# Screen_Driver.net
KiCad netlist of a schematic drawn in Altium Designer
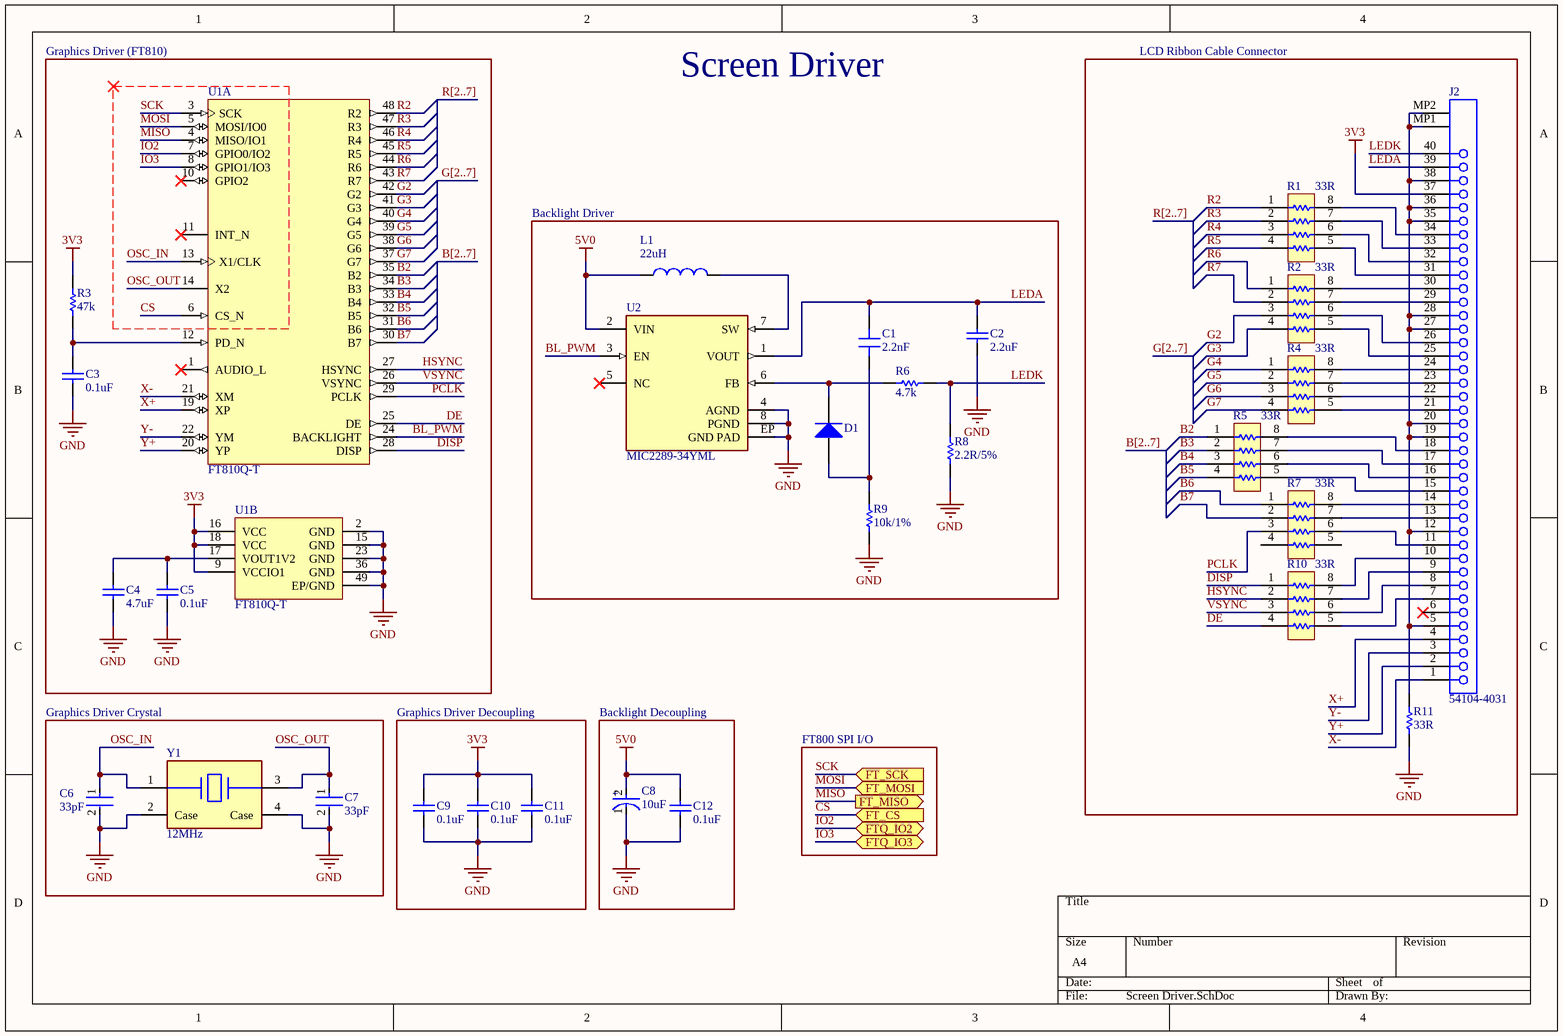
[diagram p0: Screen Driver.SchDoc]

(export (version "E")
  (design (tool "Eeschema 10.0.6"))
  (components
    (comp (ref "C1")
      (value "2.2nF")
      (footprint "0805")
      (description "CAP CER 2200PF 50V X7R 0805")
      (fields
        (field (name "MANUFACTURER") "Samsung")
        (field (name "MANUFACTURER PART NUMBER") "CL21B222KBANNNC")
      )
      (libsource (lib "Dummy Parts") (part "Capacitor - Ceramic"))
    )
    (comp (ref "C2")
      (value "2.2uF")
      (footprint "CAPC3225X270X30ML30")
      (description "Chip Capacitor, 22 uF, +/- 10%, 25 V, -55 to 125 degC, 1210 (3225 Metric), RoHS, Tape and Reel")
      (fields
        (field (name "MANUFACTURER") "Murata")
        (field (name "MANUFACTURER PART NUMBER") "GRM32ER71E226KE15L")
      )
      (libsource (lib "Altium Content Vault") (part "CAP-NP-2"))
    )
    (comp (ref "C3")
      (value "0.1uF")
      (footprint "CAPC2013X88X50NL20T25")
      (fields
        (field (name "PART NUMBER") "C0805C104K5RACTU")
        (field (name "MANUFACTURER") "Kemet")
        (field (name "TOLERANCE") "10%")
      )
      (libsource (lib "Altium Content Vault") (part "CAP"))
    )
    (comp (ref "C4")
      (value "4.7uF")
      (footprint "CAPC2113X120X50LL20T30")
      (fields
        (field (name "PART NUMBER") "TAJR475K006RNJ")
        (field (name "MANUFACTURER") "AVX Interconnect / Elco")
        (field (name "TOLERANCE") "10%")
      )
      (libsource (lib "Altium Content Vault") (part "CAP"))
    )
    (comp (ref "C5")
      (value "0.1uF")
      (footprint "CAPC2013X88X50NL20T25")
      (fields
        (field (name "PART NUMBER") "C0805C104K5RACTU")
        (field (name "MANUFACTURER") "Kemet")
        (field (name "TOLERANCE") "10%")
      )
      (libsource (lib "Altium Content Vault") (part "CAP"))
    )
    (comp (ref "C6")
      (value "33pF")
      (footprint "FP-CL21-IPC_B")
      (description "CL21 Series 0805 33pF 50V ±5% Tolerance C0G Multilayer Ceramic Chip Capacitor")
      (fields (field (name "TOLERANCE") "5%") (field (name "VOLTAGE") "50V"))
      (libsource (lib "Altium Content Vault") (part "b4654b650e69147ec39a6b967a45e02"))
    )
    (comp (ref "C7")
      (value "33pF")
      (footprint "FP-CL21-IPC_B")
      (description "CL21 Series 0805 33pF 50V ±5% Tolerance C0G Multilayer Ceramic Chip Capacitor")
      (fields (field (name "TOLERANCE") "5%") (field (name "VOLTAGE") "50V"))
      (libsource (lib "Altium Content Vault") (part "b4654b650e69147ec39a6b967a45e02"))
    )
    (comp (ref "C8")
      (value "10uF")
      (footprint "FP-T491C-MFG")
      (description "CAP TANT 10UF 10% 25V 2312")
      (fields (field (name "TOLERANCE") "10%") (field (name "MANUFACTURER PART NUMBER") "T491C106K025AT"))
      (libsource (lib "Altium Content Vault") (part "203bc49f2ac43e59fd269a8c329ed05"))
    )
    (comp (ref "C9")
      (value "0.1uF")
      (footprint "CAPC2013X88X50NL20T25")
      (fields
        (field (name "PART NUMBER") "C0805C104K5RACTU")
        (field (name "MANUFACTURER") "Kemet")
        (field (name "TOLERANCE") "10%")
      )
      (libsource (lib "Altium Content Vault") (part "CAP"))
    )
    (comp (ref "C10")
      (value "0.1uF")
      (footprint "CAPC2013X88X50NL20T25")
      (fields
        (field (name "PART NUMBER") "C0805C104K5RACTU")
        (field (name "MANUFACTURER") "Kemet")
        (field (name "TOLERANCE") "10%")
      )
      (libsource (lib "Altium Content Vault") (part "CAP"))
    )
    (comp (ref "C11")
      (value "0.1uF")
      (footprint "CAPC2013X88X50NL20T25")
      (fields
        (field (name "PART NUMBER") "C0805C104K5RACTU")
        (field (name "MANUFACTURER") "Kemet")
        (field (name "TOLERANCE") "10%")
      )
      (libsource (lib "Altium Content Vault") (part "CAP"))
    )
    (comp (ref "C12")
      (value "0.1uF")
      (footprint "CAPC2013X88X50NL20T25")
      (fields
        (field (name "PART NUMBER") "C0805C104K5RACTU")
        (field (name "MANUFACTURER") "Kemet")
        (field (name "TOLERANCE") "10%")
      )
      (libsource (lib "Altium Content Vault") (part "CAP"))
    )
    (comp (ref "D1")
      (value "1N4148WS-7-F")
      (footprint "DIOD-SOD323-2-A_V")
      (description "Fast Switching Diode, 75 V, 0.3 A, -65 to 150 degC, 2-Pin SOD323, RoHS, Tape and Reel")
      (fields (field (name "MANUFACTURER") "Diodes") (field (name "VOLTAGE") "75V"))
      (libsource (lib "Altium Content Vault") (part "D-AK-2"))
    )
    (comp (ref "J2")
      (value "54104-4031")
      (footprint "MOLX-54104-4031")
      (fields (field (name "MANUFACTURER") "Molex"))
      (libsource (lib "Altium Content Vault") (part "MOLX-54104-4031"))
    )
    (comp (ref "L1")
      (value "22uH")
      (footprint "*INDC2012X145N")
      (description "POWER INDUCTOR, 22UH, 0.135A, 10%, 16MHz")
      (fields
        (field (name "MANUFACTURER") "Taiyo Yuden")
        (field (name "MANUFACTURER PART NUMBER") "CB2012T220K")
      )
      (libsource (lib "CB2012T220K") (part "CB2012T220K"))
    )
    (comp (ref "R1")
      (value "33R")
      (footprint "PNSC-EXB-38V103JV-8_M")
      (description "Chip Resistor, 10 KOhm, +/- 5%, -55 to 125degC, 8-Pin SMD (4 X 0603), RoHS, Tape and Reel")
      (fields
        (field (name "MANUFACTURER") "Panasonic")
        (field (name "MANUFACTURER PART NUMBER") "EXB-38V103JV")
      )
      (libsource (lib "Altium Content Vault") (part "RES-P-8"))
    )
    (comp (ref "R2")
      (value "33R")
      (footprint "PNSC-EXB-38V103JV-8_M")
      (description "Chip Resistor, 10 KOhm, +/- 5%, -55 to 125degC, 8-Pin SMD (4 X 0603), RoHS, Tape and Reel")
      (fields
        (field (name "MANUFACTURER") "Panasonic")
        (field (name "MANUFACTURER PART NUMBER") "EXB-38V103JV")
      )
      (libsource (lib "Altium Content Vault") (part "RES-P-8"))
    )
    (comp (ref "R3")
      (value "47k")
      (footprint "0805")
      (description "Thin Film Resistors - SMD 0805 1/8W 3.3Kohms")
      (fields
        (field (name "MANUFACTURER") "Panasonic")
        (field (name "MANUFACTURER PART NUMBER") "ERA-6AEB332V")
      )
      (libsource (lib "Dummy Parts") (part "Resistor"))
    )
    (comp (ref "R4")
      (value "33R")
      (footprint "PNSC-EXB-38V103JV-8_M")
      (description "Chip Resistor, 10 KOhm, +/- 5%, -55 to 125degC, 8-Pin SMD (4 X 0603), RoHS, Tape and Reel")
      (fields
        (field (name "MANUFACTURER") "Panasonic")
        (field (name "MANUFACTURER PART NUMBER") "EXB-38V103JV")
      )
      (libsource (lib "Altium Content Vault") (part "RES-P-8"))
    )
    (comp (ref "R5")
      (value "33R")
      (footprint "PNSC-EXB-38V103JV-8_M")
      (description "Chip Resistor, 10 KOhm, +/- 5%, -55 to 125degC, 8-Pin SMD (4 X 0603), RoHS, Tape and Reel")
      (fields
        (field (name "MANUFACTURER") "Panasonic")
        (field (name "MANUFACTURER PART NUMBER") "EXB-38V103JV")
      )
      (libsource (lib "Altium Content Vault") (part "RES-P-8"))
    )
    (comp (ref "R6")
      (value "4.7k")
      (footprint "0805")
      (description "Thick Film Resistors - SMD 0805 4.7Kohms 5% AEC-Q200")
      (fields
        (field (name "MANUFACTURER") "Panasonic")
        (field (name "MANUFACTURER PART NUMBER") "ERJ-6GEYJ472V")
      )
      (libsource (lib "Dummy Parts") (part "Resistor"))
    )
    (comp (ref "R7")
      (value "33R")
      (footprint "PNSC-EXB-38V103JV-8_M")
      (description "Chip Resistor, 10 KOhm, +/- 5%, -55 to 125degC, 8-Pin SMD (4 X 0603), RoHS, Tape and Reel")
      (fields
        (field (name "MANUFACTURER") "Panasonic")
        (field (name "MANUFACTURER PART NUMBER") "EXB-38V103JV")
      )
      (libsource (lib "Altium Content Vault") (part "RES-P-8"))
    )
    (comp (ref "R8")
      (value "2.2R/5%")
      (footprint "0805")
      (description "Resistor;  Thick Film;  Res 2.2 Ohms;  Pwr-Rtg 0.125 W;  Tol 5%;  SMT;  0805;  Tape & Reel")
      (fields
        (field (name "MANUFACTURER") "Panasonic")
        (field (name "MANUFACTURER PART NUMBER") "ERJ-6GEYJ2R2V")
      )
      (libsource (lib "Dummy Parts") (part "Resistor"))
    )
    (comp (ref "R9")
      (value "10k/1%")
      (footprint "0805")
      (fields
        (field (name "MANUFACTURER") "Panasonic")
        (field (name "MANUFACTURER PART NUMBER") "ERJ-6ENF1002V")
        (field (name "TOLERANCE") "1%")
      )
      (libsource (lib "Dummy Parts") (part "Resistor"))
    )
    (comp (ref "R10")
      (value "33R")
      (footprint "PNSC-EXB-38V103JV-8_M")
      (description "Chip Resistor, 10 KOhm, +/- 5%, -55 to 125degC, 8-Pin SMD (4 X 0603), RoHS, Tape and Reel")
      (fields
        (field (name "MANUFACTURER") "Panasonic")
        (field (name "MANUFACTURER PART NUMBER") "EXB-38V103JV")
      )
      (libsource (lib "Altium Content Vault") (part "RES-P-8"))
    )
    (comp (ref "R11")
      (value "33R")
      (footprint "0805")
      (description "Res Thick Film 0805 33 Ohm 1% 0.125W(1/8W) ±100ppm/C Molded SMD Automotive Punched T/R")
      (fields
        (field (name "MANUFACTURER") "Panasonic")
        (field (name "MANUFACTURER PART NUMBER") "ERJ-6ENF33R0V")
      )
      (libsource (lib "Dummy Parts") (part "Resistor"))
    )
    (comp (ref "U1")
      (value "FT810Q-T")
      (footprint "VQFN-48_5.2x5.2EP")
      (fields (field (name "MANUFACTURER") "FTDI"))
      (libsource (lib "Altium Content Vault") (part "FT810Q"))
    )
    (comp (ref "U2")
      (value "MIC2289")
      (footprint "MIC2289")
      (fields
        (field (name "MANUFACTURER") "Microchip")
        (field (name "MOUSER PART NUMBER") "998-MIC2289-34YMLTR")
        (field (name "DIGIKEY PART NUMBER") "576-1732-1-ND")
        (field (name "PART NUMBER") "MIC2289-34YML")
      )
      (libsource (lib "MIC2289") (part "MIC2289"))
    )
    (comp (ref "Y1")
      (value "12MHz")
      (footprint "FP-FL1200112-MFG")
      (description "CRYSTAL 12MHZ 18PF SMD")
      (fields (field (name "MANUFACTURER") "Diodes") (field (name "MANUFACTURER PART NUMBER") "FL1200112"))
      (libsource (lib "Altium Content Vault") (part "5207c8a21b287eb3b87797a81180633"))
    )
  )
  (nets
    (net (code "1") (name "/B2") (class "Default")
      (node (ref "R5") (pin "1") (pinfunction "1_1") (pintype "passive"))
      (node (ref "U1") (pin "35") (pinfunction "B2_35") (pintype "output"))
    )
    (net (code "2") (name "/B3") (class "Default")
      (node (ref "R5") (pin "2") (pinfunction "2_2") (pintype "passive"))
      (node (ref "U1") (pin "34") (pinfunction "B3_34") (pintype "output"))
    )
    (net (code "3") (name "/B4") (class "Default")
      (node (ref "R5") (pin "3") (pinfunction "3_3") (pintype "passive"))
      (node (ref "U1") (pin "33") (pinfunction "B4_33") (pintype "output"))
    )
    (net (code "4") (name "/B5") (class "Default")
      (node (ref "R5") (pin "4") (pinfunction "4_4") (pintype "passive"))
      (node (ref "U1") (pin "32") (pinfunction "B5_32") (pintype "output"))
    )
    (net (code "5") (name "/B6") (class "Default")
      (node (ref "R7") (pin "1") (pinfunction "1_1") (pintype "passive"))
      (node (ref "U1") (pin "31") (pinfunction "B6_31") (pintype "output"))
    )
    (net (code "6") (name "/B7") (class "Default")
      (node (ref "R7") (pin "2") (pinfunction "2_2") (pintype "passive"))
      (node (ref "U1") (pin "30") (pinfunction "B7_30") (pintype "output"))
    )
    (net (code "7") (name "/BL_PWM") (class "Default")
      (node (ref "U1") (pin "24") (pinfunction "BACKLIGHT_24") (pintype "output"))
      (node (ref "U2") (pin "3") (pinfunction "EN_3") (pintype "input"))
    )
    (net (code "9") (name "/CS") (class "Default")
      (node (ref "U1") (pin "6") (pinfunction "CS_N_6") (pintype "input"))
    )
    (net (code "10") (name "/DE") (class "Default")
      (node (ref "R10") (pin "4") (pinfunction "4_4") (pintype "passive"))
      (node (ref "U1") (pin "25") (pinfunction "DE_25") (pintype "output"))
    )
    (net (code "11") (name "/DISP") (class "Default")
      (node (ref "R10") (pin "1") (pinfunction "1_1") (pintype "passive"))
      (node (ref "U1") (pin "28") (pinfunction "DISP_28") (pintype "output"))
    )
    (net (code "12") (name "/G2") (class "Default")
      (node (ref "R2") (pin "3") (pinfunction "3_3") (pintype "passive"))
      (node (ref "U1") (pin "42") (pinfunction "G2_42") (pintype "output"))
    )
    (net (code "13") (name "/G3") (class "Default")
      (node (ref "R2") (pin "4") (pinfunction "4_4") (pintype "passive"))
      (node (ref "U1") (pin "41") (pinfunction "G3_41") (pintype "output"))
    )
    (net (code "14") (name "/G4") (class "Default")
      (node (ref "R4") (pin "1") (pinfunction "1_1") (pintype "passive"))
      (node (ref "U1") (pin "40") (pinfunction "G4_40") (pintype "output"))
    )
    (net (code "15") (name "/G5") (class "Default")
      (node (ref "R4") (pin "2") (pinfunction "2_2") (pintype "passive"))
      (node (ref "U1") (pin "39") (pinfunction "G5_39") (pintype "output"))
    )
    (net (code "16") (name "/G6") (class "Default")
      (node (ref "R4") (pin "3") (pinfunction "3_3") (pintype "passive"))
      (node (ref "U1") (pin "38") (pinfunction "G6_38") (pintype "output"))
    )
    (net (code "17") (name "/G7") (class "Default")
      (node (ref "R4") (pin "4") (pinfunction "4_4") (pintype "passive"))
      (node (ref "U1") (pin "37") (pinfunction "G7_37") (pintype "output"))
    )
    (net (code "19") (name "/HSYNC") (class "Default")
      (node (ref "R10") (pin "2") (pinfunction "2_2") (pintype "passive"))
      (node (ref "U1") (pin "27") (pinfunction "HSYNC_27") (pintype "output"))
    )
    (net (code "20") (name "/IO2") (class "Default")
      (node (ref "U1") (pin "7") (pinfunction "GPIO0/IO2_7") (pintype "bidirectional"))
    )
    (net (code "21") (name "/IO3") (class "Default")
      (node (ref "U1") (pin "8") (pinfunction "GPIO1/IO3_8") (pintype "bidirectional"))
    )
    (net (code "22") (name "/LEDA") (class "Default")
      (node (ref "C1") (pin "2") (pinfunction "2_2") (pintype "passive"))
      (node (ref "C2") (pin "2") (pinfunction "2_2") (pintype "passive"))
      (node (ref "J2") (pin "39") (pinfunction "39_39") (pintype "passive"))
      (node (ref "U2") (pin "1") (pinfunction "VOUT_1") (pintype "output"))
    )
    (net (code "23") (name "/LEDK") (class "Default")
      (node (ref "J2") (pin "40") (pinfunction "40_40") (pintype "passive"))
      (node (ref "R6") (pin "1") (pinfunction "1_1") (pintype "passive"))
      (node (ref "R8") (pin "1") (pinfunction "1_1") (pintype "passive"))
    )
    (net (code "24") (name "/MISO") (class "Default")
      (node (ref "U1") (pin "4") (pinfunction "MISO/IO1_4") (pintype "bidirectional"))
    )
    (net (code "25") (name "/MOSI") (class "Default")
      (node (ref "U1") (pin "5") (pinfunction "MOSI/IO0_5") (pintype "bidirectional"))
    )
    (net (code "26") (name "/OSC_IN") (class "Default")
      (node (ref "C6") (pin "1") (pinfunction "1_1") (pintype "passive"))
      (node (ref "U1") (pin "13") (pinfunction "X1/CLK_13") (pintype "input"))
      (node (ref "Y1") (pin "1") (pinfunction "1_Xtal_1") (pintype "passive"))
    )
    (net (code "27") (name "/OSC_OUT") (class "Default")
      (node (ref "C7") (pin "1") (pinfunction "1_1") (pintype "passive"))
      (node (ref "U1") (pin "14") (pinfunction "X2_14") (pintype "passive"))
      (node (ref "Y1") (pin "3") (pinfunction "2_Xtal_3") (pintype "passive"))
    )
    (net (code "28") (name "/PCLK") (class "Default")
      (node (ref "R7") (pin "3") (pinfunction "3_3") (pintype "passive"))
      (node (ref "U1") (pin "29") (pinfunction "PCLK_29") (pintype "output"))
    )
    (net (code "29") (name "/R2") (class "Default")
      (node (ref "R1") (pin "1") (pinfunction "1_1") (pintype "passive"))
      (node (ref "U1") (pin "48") (pinfunction "R2_48") (pintype "output"))
    )
    (net (code "30") (name "/R3") (class "Default")
      (node (ref "R1") (pin "2") (pinfunction "2_2") (pintype "passive"))
      (node (ref "U1") (pin "47") (pinfunction "R3_47") (pintype "output"))
    )
    (net (code "31") (name "/R4") (class "Default")
      (node (ref "R1") (pin "3") (pinfunction "3_3") (pintype "passive"))
      (node (ref "U1") (pin "46") (pinfunction "R4_46") (pintype "output"))
    )
    (net (code "32") (name "/R5") (class "Default")
      (node (ref "R1") (pin "4") (pinfunction "4_4") (pintype "passive"))
      (node (ref "U1") (pin "45") (pinfunction "R5_45") (pintype "output"))
    )
    (net (code "33") (name "/R6") (class "Default")
      (node (ref "R2") (pin "1") (pinfunction "1_1") (pintype "passive"))
      (node (ref "U1") (pin "44") (pinfunction "R6_44") (pintype "output"))
    )
    (net (code "34") (name "/R7") (class "Default")
      (node (ref "R2") (pin "2") (pinfunction "2_2") (pintype "passive"))
      (node (ref "U1") (pin "43") (pinfunction "R7_43") (pintype "output"))
    )
    (net (code "36") (name "/SCK") (class "Default")
      (node (ref "U1") (pin "3") (pinfunction "SCK_3") (pintype "input"))
    )
    (net (code "37") (name "/VSYNC") (class "Default")
      (node (ref "R10") (pin "3") (pinfunction "3_3") (pintype "passive"))
      (node (ref "U1") (pin "26") (pinfunction "VSYNC_26") (pintype "output"))
    )
    (net (code "38") (name "/X+") (class "Default")
      (node (ref "J2") (pin "4") (pinfunction "4_4") (pintype "passive"))
      (node (ref "U1") (pin "19") (pinfunction "XP_19") (pintype "bidirectional"))
    )
    (net (code "39") (name "/X-") (class "Default")
      (node (ref "J2") (pin "1") (pinfunction "1_1") (pintype "passive"))
      (node (ref "U1") (pin "21") (pinfunction "XM_21") (pintype "bidirectional"))
    )
    (net (code "40") (name "/Y+") (class "Default")
      (node (ref "J2") (pin "2") (pinfunction "2_2") (pintype "passive"))
      (node (ref "U1") (pin "20") (pinfunction "YP_20") (pintype "bidirectional"))
    )
    (net (code "41") (name "/Y-") (class "Default")
      (node (ref "J2") (pin "3") (pinfunction "3_3") (pintype "passive"))
      (node (ref "U1") (pin "22") (pinfunction "YM_22") (pintype "bidirectional"))
    )
    (net (code "42") (name "3V3") (class "Default")
      (node (ref "C10") (pin "2") (pinfunction "2_2") (pintype "passive"))
      (node (ref "C11") (pin "2") (pinfunction "2_2") (pintype "passive"))
      (node (ref "C9") (pin "2") (pinfunction "2_2") (pintype "passive"))
      (node (ref "J2") (pin "37") (pinfunction "37_37") (pintype "passive"))
      (node (ref "R3") (pin "2") (pinfunction "2_2") (pintype "passive"))
      (node (ref "U1") (pin "16") (pinfunction "VCC_16") (pintype "power_in"))
      (node (ref "U1") (pin "18") (pinfunction "VCC_18") (pintype "power_in"))
      (node (ref "U1") (pin "9") (pinfunction "VCCIO1_9") (pintype "power_in"))
    )
    (net (code "43") (name "5V0") (class "Default")
      (node (ref "C12") (pin "2") (pinfunction "2_2") (pintype "passive"))
      (node (ref "C8") (pin "2") (pinfunction "A_2") (pintype "passive"))
      (node (ref "L1") (pin "1") (pinfunction "1_1") (pintype "passive"))
      (node (ref "U2") (pin "2") (pinfunction "VIN_2") (pintype "power_in"))
    )
    (net (code "44") (name "GND") (class "Default")
      (node (ref "C10") (pin "1") (pinfunction "1_1") (pintype "passive"))
      (node (ref "C11") (pin "1") (pinfunction "1_1") (pintype "passive"))
      (node (ref "C12") (pin "1") (pinfunction "1_1") (pintype "passive"))
      (node (ref "C2") (pin "1") (pinfunction "1_1") (pintype "passive"))
      (node (ref "C3") (pin "1") (pinfunction "1_1") (pintype "passive"))
      (node (ref "C4") (pin "1") (pinfunction "1_1") (pintype "passive"))
      (node (ref "C5") (pin "1") (pinfunction "1_1") (pintype "passive"))
      (node (ref "C6") (pin "2") (pinfunction "2_2") (pintype "passive"))
      (node (ref "C7") (pin "2") (pinfunction "2_2") (pintype "passive"))
      (node (ref "C8") (pin "1") (pinfunction "C_1") (pintype "passive"))
      (node (ref "C9") (pin "1") (pinfunction "1_1") (pintype "passive"))
      (node (ref "R11") (pin "1") (pinfunction "1_1") (pintype "passive"))
      (node (ref "R8") (pin "2") (pinfunction "2_2") (pintype "passive"))
      (node (ref "R9") (pin "1") (pinfunction "1_1") (pintype "passive"))
      (node (ref "U1") (pin "15") (pinfunction "GND_15") (pintype "power_in"))
      (node (ref "U1") (pin "2") (pinfunction "GND_2") (pintype "power_in"))
      (node (ref "U1") (pin "23") (pinfunction "GND_23") (pintype "power_in"))
      (node (ref "U1") (pin "36") (pinfunction "GND_36") (pintype "power_in"))
      (node (ref "U1") (pin "49") (pinfunction "EP/GND_49") (pintype "power_in"))
      (node (ref "U2") (pin "4") (pinfunction "AGND_4") (pintype "power_in"))
      (node (ref "U2") (pin "8") (pinfunction "PGND_8") (pintype "power_in"))
      (node (ref "U2") (pin "EP") (pinfunction "GND_PAD_EP") (pintype "power_in"))
      (node (ref "Y1") (pin "2") (pinfunction "Case_2") (pintype "passive"))
      (node (ref "Y1") (pin "4") (pinfunction "Case_4") (pintype "passive"))
    )
    (net (code "45") (name "Net-(D1-A)") (class "Default")
      (node (ref "C1") (pin "1") (pinfunction "1_1") (pintype "passive"))
      (node (ref "D1") (pin "1") (pinfunction "A_1") (pintype "passive"))
      (node (ref "R9") (pin "2") (pinfunction "2_2") (pintype "passive"))
    )
    (net (code "46") (name "Net-(D1-K)") (class "Default")
      (node (ref "D1") (pin "2") (pinfunction "K_2") (pintype "passive"))
      (node (ref "R6") (pin "2") (pinfunction "2_2") (pintype "passive"))
      (node (ref "U2") (pin "6") (pinfunction "FB_6") (pintype "input"))
    )
    (net (code "47") (name "Net-(J2-Pad7)") (class "Default")
      (node (ref "J2") (pin "7") (pinfunction "7_7") (pintype "passive"))
      (node (ref "R10") (pin "5") (pinfunction "5_5") (pintype "passive"))
    )
    (net (code "48") (name "Net-(J2-Pad8)") (class "Default")
      (node (ref "J2") (pin "8") (pinfunction "8_8") (pintype "passive"))
      (node (ref "R10") (pin "6") (pinfunction "6_6") (pintype "passive"))
    )
    (net (code "49") (name "Net-(J2-Pad9)") (class "Default")
      (node (ref "J2") (pin "9") (pinfunction "9_9") (pintype "passive"))
      (node (ref "R10") (pin "7") (pinfunction "7_7") (pintype "passive"))
    )
    (net (code "50") (name "Net-(J2-Pad10)") (class "Default")
      (node (ref "J2") (pin "10") (pinfunction "10_10") (pintype "passive"))
      (node (ref "R10") (pin "8") (pinfunction "8_8") (pintype "passive"))
    )
    (net (code "51") (name "Net-(J2-Pad11)") (class "Default")
      (node (ref "J2") (pin "11") (pinfunction "11_11") (pintype "passive"))
      (node (ref "R7") (pin "6") (pinfunction "6_6") (pintype "passive"))
    )
    (net (code "52") (name "Net-(J2-Pad12)") (class "Default")
      (node (ref "J2") (pin "12") (pinfunction "12_12") (pintype "passive"))
      (node (ref "J2") (pin "19") (pinfunction "19_19") (pintype "passive"))
      (node (ref "J2") (pin "20") (pinfunction "20_20") (pintype "passive"))
      (node (ref "J2") (pin "27") (pinfunction "27_27") (pintype "passive"))
      (node (ref "J2") (pin "28") (pinfunction "28_28") (pintype "passive"))
      (node (ref "J2") (pin "35") (pinfunction "35_35") (pintype "passive"))
      (node (ref "J2") (pin "36") (pinfunction "36_36") (pintype "passive"))
      (node (ref "J2") (pin "38") (pinfunction "38_38") (pintype "passive"))
      (node (ref "J2") (pin "5") (pinfunction "5_5") (pintype "passive"))
      (node (ref "J2") (pin "MP1") (pinfunction "MP1_MP1") (pintype "passive"))
      (node (ref "J2") (pin "MP2") (pinfunction "MP2_MP2") (pintype "passive"))
      (node (ref "R11") (pin "2") (pinfunction "2_2") (pintype "passive"))
    )
    (net (code "53") (name "Net-(J2-Pad13)") (class "Default")
      (node (ref "J2") (pin "13") (pinfunction "13_13") (pintype "passive"))
      (node (ref "R7") (pin "7") (pinfunction "7_7") (pintype "passive"))
    )
    (net (code "54") (name "Net-(J2-Pad14)") (class "Default")
      (node (ref "J2") (pin "14") (pinfunction "14_14") (pintype "passive"))
      (node (ref "R7") (pin "8") (pinfunction "8_8") (pintype "passive"))
    )
    (net (code "55") (name "Net-(J2-Pad15)") (class "Default")
      (node (ref "J2") (pin "15") (pinfunction "15_15") (pintype "passive"))
      (node (ref "R5") (pin "5") (pinfunction "5_5") (pintype "passive"))
    )
    (net (code "56") (name "Net-(J2-Pad16)") (class "Default")
      (node (ref "J2") (pin "16") (pinfunction "16_16") (pintype "passive"))
      (node (ref "R5") (pin "6") (pinfunction "6_6") (pintype "passive"))
    )
    (net (code "57") (name "Net-(J2-Pad17)") (class "Default")
      (node (ref "J2") (pin "17") (pinfunction "17_17") (pintype "passive"))
      (node (ref "R5") (pin "7") (pinfunction "7_7") (pintype "passive"))
    )
    (net (code "58") (name "Net-(J2-Pad18)") (class "Default")
      (node (ref "J2") (pin "18") (pinfunction "18_18") (pintype "passive"))
      (node (ref "R5") (pin "8") (pinfunction "8_8") (pintype "passive"))
    )
    (net (code "59") (name "Net-(J2-Pad21)") (class "Default")
      (node (ref "J2") (pin "21") (pinfunction "21_21") (pintype "passive"))
      (node (ref "R4") (pin "5") (pinfunction "5_5") (pintype "passive"))
    )
    (net (code "60") (name "Net-(J2-Pad22)") (class "Default")
      (node (ref "J2") (pin "22") (pinfunction "22_22") (pintype "passive"))
      (node (ref "R4") (pin "6") (pinfunction "6_6") (pintype "passive"))
    )
    (net (code "61") (name "Net-(J2-Pad23)") (class "Default")
      (node (ref "J2") (pin "23") (pinfunction "23_23") (pintype "passive"))
      (node (ref "R4") (pin "7") (pinfunction "7_7") (pintype "passive"))
    )
    (net (code "62") (name "Net-(J2-Pad24)") (class "Default")
      (node (ref "J2") (pin "24") (pinfunction "24_24") (pintype "passive"))
      (node (ref "R4") (pin "8") (pinfunction "8_8") (pintype "passive"))
    )
    (net (code "63") (name "Net-(J2-Pad25)") (class "Default")
      (node (ref "J2") (pin "25") (pinfunction "25_25") (pintype "passive"))
      (node (ref "R2") (pin "5") (pinfunction "5_5") (pintype "passive"))
    )
    (net (code "64") (name "Net-(J2-Pad26)") (class "Default")
      (node (ref "J2") (pin "26") (pinfunction "26_26") (pintype "passive"))
      (node (ref "R2") (pin "6") (pinfunction "6_6") (pintype "passive"))
    )
    (net (code "65") (name "Net-(J2-Pad29)") (class "Default")
      (node (ref "J2") (pin "29") (pinfunction "29_29") (pintype "passive"))
      (node (ref "R2") (pin "7") (pinfunction "7_7") (pintype "passive"))
    )
    (net (code "66") (name "Net-(J2-Pad30)") (class "Default")
      (node (ref "J2") (pin "30") (pinfunction "30_30") (pintype "passive"))
      (node (ref "R2") (pin "8") (pinfunction "8_8") (pintype "passive"))
    )
    (net (code "67") (name "Net-(J2-Pad31)") (class "Default")
      (node (ref "J2") (pin "31") (pinfunction "31_31") (pintype "passive"))
      (node (ref "R1") (pin "5") (pinfunction "5_5") (pintype "passive"))
    )
    (net (code "68") (name "Net-(J2-Pad32)") (class "Default")
      (node (ref "J2") (pin "32") (pinfunction "32_32") (pintype "passive"))
      (node (ref "R1") (pin "6") (pinfunction "6_6") (pintype "passive"))
    )
    (net (code "69") (name "Net-(J2-Pad33)") (class "Default")
      (node (ref "J2") (pin "33") (pinfunction "33_33") (pintype "passive"))
      (node (ref "R1") (pin "7") (pinfunction "7_7") (pintype "passive"))
    )
    (net (code "70") (name "Net-(J2-Pad34)") (class "Default")
      (node (ref "J2") (pin "34") (pinfunction "34_34") (pintype "passive"))
      (node (ref "R1") (pin "8") (pinfunction "8_8") (pintype "passive"))
    )
    (net (code "71") (name "Net-(U1A-PD_N)") (class "Default")
      (node (ref "C3") (pin "2") (pinfunction "2_2") (pintype "passive"))
      (node (ref "R3") (pin "1") (pinfunction "1_1") (pintype "passive"))
      (node (ref "U1") (pin "12") (pinfunction "PD_N_12") (pintype "input"))
    )
    (net (code "72") (name "Net-(U1B-VOUT1V2)") (class "Default")
      (node (ref "C4") (pin "2") (pinfunction "2_2") (pintype "passive"))
      (node (ref "C5") (pin "2") (pinfunction "2_2") (pintype "passive"))
      (node (ref "U1") (pin "17") (pinfunction "VOUT1V2_17") (pintype "power_in"))
    )
    (net (code "73") (name "Net-(U2-SW)") (class "Default")
      (node (ref "L1") (pin "2") (pinfunction "2_2") (pintype "passive"))
      (node (ref "U2") (pin "7") (pinfunction "SW_7") (pintype "input"))
    )
    (net (code "74") (name "unconnected-(J2-Pad6)") (class "Default")
      (node (ref "J2") (pin "6") (pinfunction "6_6") (pintype "passive+no_connect"))
    )
    (net (code "75") (name "unconnected-(R7-Pad4)") (class "Default")
      (node (ref "R7") (pin "4") (pinfunction "4_4") (pintype "passive"))
    )
    (net (code "76") (name "unconnected-(R7-Pad5)") (class "Default")
      (node (ref "R7") (pin "5") (pinfunction "5_5") (pintype "passive"))
    )
    (net (code "77") (name "unconnected-(U1A-AUDIO_L-Pad1)") (class "Default")
      (node (ref "U1") (pin "1") (pinfunction "AUDIO_L_1") (pintype "output+no_connect"))
    )
    (net (code "78") (name "unconnected-(U1A-GPIO2-Pad10)") (class "Default")
      (node (ref "U1") (pin "10") (pinfunction "GPIO2_10") (pintype "bidirectional+no_connect"))
    )
    (net (code "79") (name "unconnected-(U1A-INT_N-Pad11)") (class "Default")
      (node (ref "U1") (pin "11") (pinfunction "INT_N_11") (pintype "passive+no_connect"))
    )
    (net (code "80") (name "unconnected-(U2-NC-Pad5)") (class "Default")
      (node (ref "U2") (pin "5") (pinfunction "NC_5") (pintype "passive+no_connect"))
    )
  )
)
